# Demo_Board_3_-_Schematic.net
KiCad netlist of a schematic drawn in Altium Designer
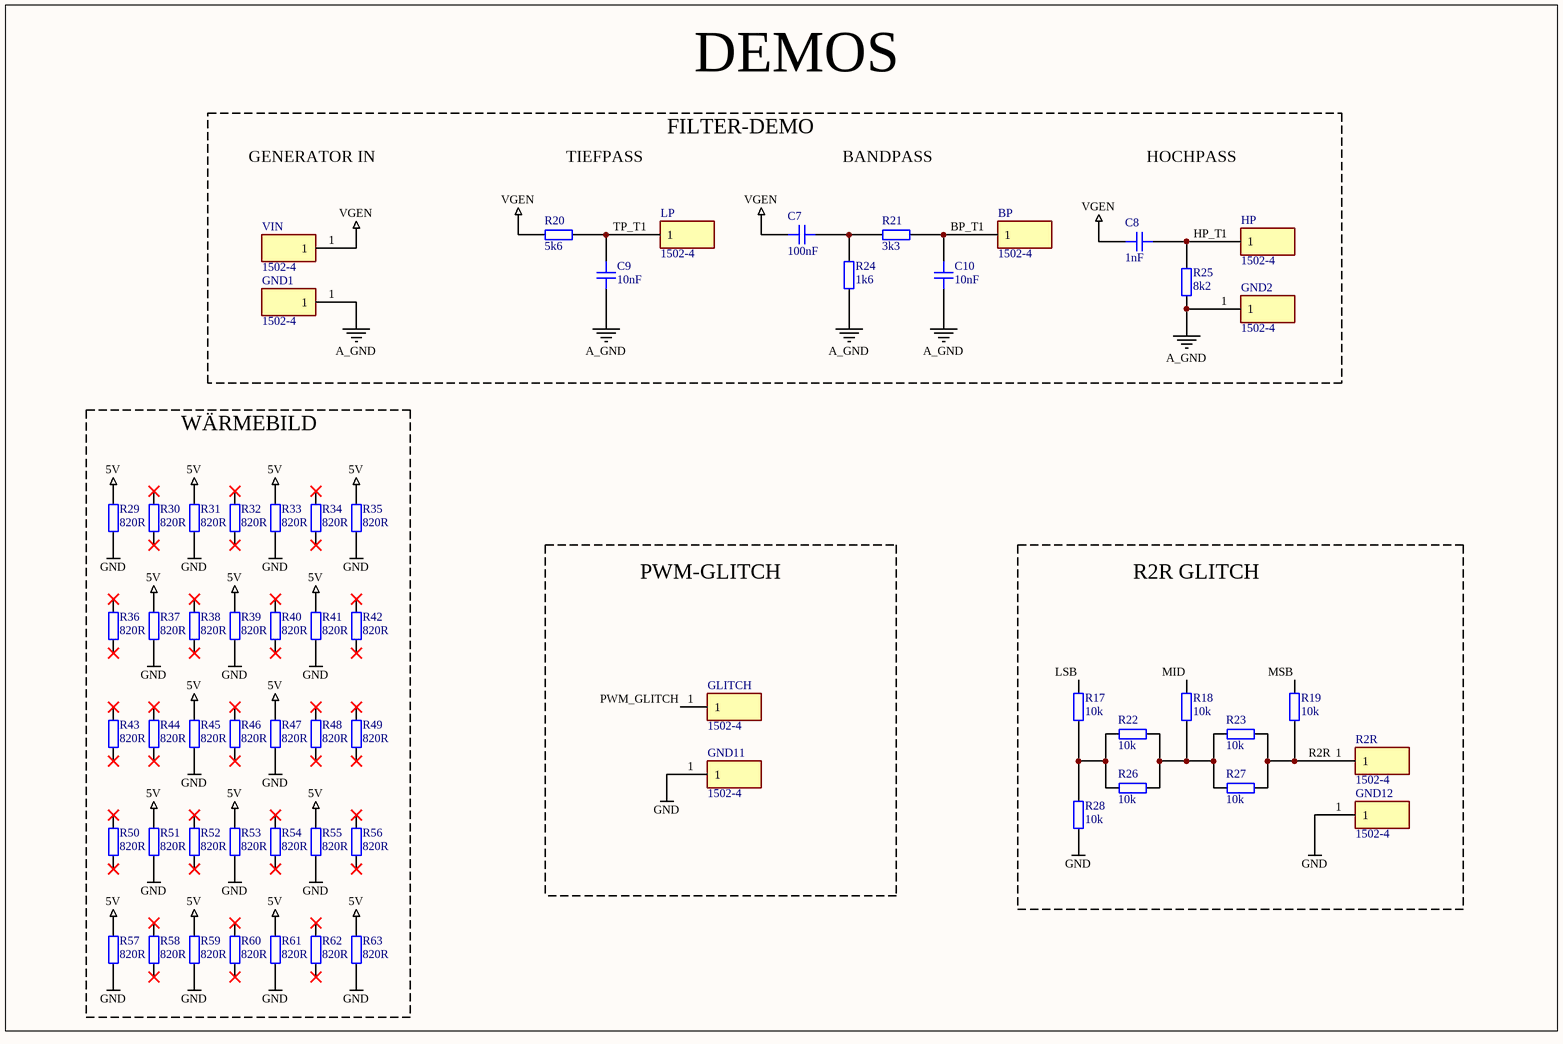
[diagram p0: Demo Board 3 - Schematic.SchDoc]

(export (version "E")
  (design (tool "Eeschema 10.0.6"))
  (components
    (comp (ref "BP")
      (value "1502-4")
      (footprint "KEYSTONE_1502-4")
      (libsource (lib "1502-4") (part "1502-4"))
    )
    (comp (ref "C7")
      (value "100nF")
      (footprint "CAP_0603")
      (description "Capacitor SMD 0603")
      (libsource (lib "Auer Library") (part "CAP_0603"))
    )
    (comp (ref "C8")
      (value "1nF")
      (footprint "CAP_0603")
      (description "Capacitor SMD 0603")
      (libsource (lib "Auer Library") (part "CAP_0603"))
    )
    (comp (ref "C9")
      (value "10nF")
      (footprint "CAP_0603")
      (description "Capacitor SMD 0603")
      (libsource (lib "Auer Library") (part "CAP_0603"))
    )
    (comp (ref "C10")
      (value "10nF")
      (footprint "CAP_0603")
      (description "Capacitor SMD 0603")
      (libsource (lib "Auer Library") (part "CAP_0603"))
    )
    (comp (ref "GLITCH")
      (value "1502-4")
      (footprint "KEYSTONE_1502-4")
      (libsource (lib "1502-4") (part "1502-4"))
    )
    (comp (ref "GND1") (value "1502-4") (footprint "KEYSTONE_1502-4") (libsource (lib "") (part "1502-4_1")))
    (comp (ref "GND2")
      (value "1502-4")
      (footprint "KEYSTONE_1502-4")
      (libsource (lib "1502-4") (part "1502-4"))
    )
    (comp (ref "GND11")
      (value "1502-4")
      (footprint "KEYSTONE_1502-4")
      (libsource (lib "1502-4") (part "1502-4"))
    )
    (comp (ref "GND12")
      (value "1502-4")
      (footprint "KEYSTONE_1502-4")
      (libsource (lib "1502-4") (part "1502-4"))
    )
    (comp (ref "HP")
      (value "1502-4")
      (footprint "KEYSTONE_1502-4")
      (libsource (lib "1502-4") (part "1502-4"))
    )
    (comp (ref "LP")
      (value "1502-4")
      (footprint "KEYSTONE_1502-4")
      (libsource (lib "1502-4") (part "1502-4"))
    )
    (comp (ref "R2R")
      (value "1502-4")
      (footprint "KEYSTONE_1502-4")
      (libsource (lib "1502-4") (part "1502-4"))
    )
    (comp (ref "R17")
      (value "10k")
      (footprint "RES_0603")
      (description "Resistor SMD 0603")
      (libsource (lib "Auer Library") (part "RES_0603"))
    )
    (comp (ref "R18")
      (value "10k")
      (footprint "RES_0603")
      (description "Resistor SMD 0603")
      (libsource (lib "Auer Library") (part "RES_0603"))
    )
    (comp (ref "R19")
      (value "10k")
      (footprint "RES_0603")
      (description "Resistor SMD 0603")
      (libsource (lib "Auer Library") (part "RES_0603"))
    )
    (comp (ref "R20")
      (value "5k6")
      (footprint "RES_0603")
      (description "Resistor SMD 0603")
      (libsource (lib "Auer Library") (part "RES_0603"))
    )
    (comp (ref "R21")
      (value "3k3")
      (footprint "RES_0603")
      (description "Resistor SMD 0603")
      (libsource (lib "Auer Library") (part "RES_0603"))
    )
    (comp (ref "R22")
      (value "10k")
      (footprint "RES_0603")
      (description "Resistor SMD 0603")
      (libsource (lib "Auer Library") (part "RES_0603"))
    )
    (comp (ref "R23")
      (value "10k")
      (footprint "RES_0603")
      (description "Resistor SMD 0603")
      (libsource (lib "Auer Library") (part "RES_0603"))
    )
    (comp (ref "R24")
      (value "1k6")
      (footprint "RES_0603")
      (description "Resistor SMD 0603")
      (libsource (lib "Auer Library") (part "RES_0603"))
    )
    (comp (ref "R25")
      (value "8k2")
      (footprint "RES_0603")
      (description "Resistor SMD 0603")
      (libsource (lib "Auer Library") (part "RES_0603"))
    )
    (comp (ref "R26")
      (value "10k")
      (footprint "RES_0603")
      (description "Resistor SMD 0603")
      (libsource (lib "Auer Library") (part "RES_0603"))
    )
    (comp (ref "R27")
      (value "10k")
      (footprint "RES_0603")
      (description "Resistor SMD 0603")
      (libsource (lib "Auer Library") (part "RES_0603"))
    )
    (comp (ref "R28")
      (value "10k")
      (footprint "RES_0603")
      (description "Resistor SMD 0603")
      (libsource (lib "Auer Library") (part "RES_0603"))
    )
    (comp (ref "R29")
      (value "820R")
      (footprint "RES_0603")
      (description "Resistor SMD 0603")
      (libsource (lib "Auer Library") (part "RES_0603"))
    )
    (comp (ref "R30")
      (value "820R")
      (footprint "RES_0603")
      (description "Resistor SMD 0603")
      (libsource (lib "Auer Library") (part "RES_0603"))
    )
    (comp (ref "R31")
      (value "820R")
      (footprint "RES_0603")
      (description "Resistor SMD 0603")
      (libsource (lib "Auer Library") (part "RES_0603"))
    )
    (comp (ref "R32")
      (value "820R")
      (footprint "RES_0603")
      (description "Resistor SMD 0603")
      (libsource (lib "Auer Library") (part "RES_0603"))
    )
    (comp (ref "R33")
      (value "820R")
      (footprint "RES_0603")
      (description "Resistor SMD 0603")
      (libsource (lib "Auer Library") (part "RES_0603"))
    )
    (comp (ref "R34")
      (value "820R")
      (footprint "RES_0603")
      (description "Resistor SMD 0603")
      (libsource (lib "Auer Library") (part "RES_0603"))
    )
    (comp (ref "R35")
      (value "820R")
      (footprint "RES_0603")
      (description "Resistor SMD 0603")
      (libsource (lib "Auer Library") (part "RES_0603"))
    )
    (comp (ref "R36")
      (value "820R")
      (footprint "RES_0603")
      (description "Resistor SMD 0603")
      (libsource (lib "Auer Library") (part "RES_0603"))
    )
    (comp (ref "R37")
      (value "820R")
      (footprint "RES_0603")
      (description "Resistor SMD 0603")
      (libsource (lib "Auer Library") (part "RES_0603"))
    )
    (comp (ref "R38")
      (value "820R")
      (footprint "RES_0603")
      (description "Resistor SMD 0603")
      (libsource (lib "Auer Library") (part "RES_0603"))
    )
    (comp (ref "R39")
      (value "820R")
      (footprint "RES_0603")
      (description "Resistor SMD 0603")
      (libsource (lib "Auer Library") (part "RES_0603"))
    )
    (comp (ref "R40")
      (value "820R")
      (footprint "RES_0603")
      (description "Resistor SMD 0603")
      (libsource (lib "Auer Library") (part "RES_0603"))
    )
    (comp (ref "R41")
      (value "820R")
      (footprint "RES_0603")
      (description "Resistor SMD 0603")
      (libsource (lib "Auer Library") (part "RES_0603"))
    )
    (comp (ref "R42")
      (value "820R")
      (footprint "RES_0603")
      (description "Resistor SMD 0603")
      (libsource (lib "Auer Library") (part "RES_0603"))
    )
    (comp (ref "R43")
      (value "820R")
      (footprint "RES_0603")
      (description "Resistor SMD 0603")
      (libsource (lib "Auer Library") (part "RES_0603"))
    )
    (comp (ref "R44")
      (value "820R")
      (footprint "RES_0603")
      (description "Resistor SMD 0603")
      (libsource (lib "Auer Library") (part "RES_0603"))
    )
    (comp (ref "R45")
      (value "820R")
      (footprint "RES_0603")
      (description "Resistor SMD 0603")
      (libsource (lib "Auer Library") (part "RES_0603"))
    )
    (comp (ref "R46")
      (value "820R")
      (footprint "RES_0603")
      (description "Resistor SMD 0603")
      (libsource (lib "Auer Library") (part "RES_0603"))
    )
    (comp (ref "R47")
      (value "820R")
      (footprint "RES_0603")
      (description "Resistor SMD 0603")
      (libsource (lib "Auer Library") (part "RES_0603"))
    )
    (comp (ref "R48")
      (value "820R")
      (footprint "RES_0603")
      (description "Resistor SMD 0603")
      (libsource (lib "Auer Library") (part "RES_0603"))
    )
    (comp (ref "R49")
      (value "820R")
      (footprint "RES_0603")
      (description "Resistor SMD 0603")
      (libsource (lib "Auer Library") (part "RES_0603"))
    )
    (comp (ref "R50")
      (value "820R")
      (footprint "RES_0603")
      (description "Resistor SMD 0603")
      (libsource (lib "Auer Library") (part "RES_0603"))
    )
    (comp (ref "R51")
      (value "820R")
      (footprint "RES_0603")
      (description "Resistor SMD 0603")
      (libsource (lib "Auer Library") (part "RES_0603"))
    )
    (comp (ref "R52")
      (value "820R")
      (footprint "RES_0603")
      (description "Resistor SMD 0603")
      (libsource (lib "Auer Library") (part "RES_0603"))
    )
    (comp (ref "R53")
      (value "820R")
      (footprint "RES_0603")
      (description "Resistor SMD 0603")
      (libsource (lib "Auer Library") (part "RES_0603"))
    )
    (comp (ref "R54")
      (value "820R")
      (footprint "RES_0603")
      (description "Resistor SMD 0603")
      (libsource (lib "Auer Library") (part "RES_0603"))
    )
    (comp (ref "R55")
      (value "820R")
      (footprint "RES_0603")
      (description "Resistor SMD 0603")
      (libsource (lib "Auer Library") (part "RES_0603"))
    )
    (comp (ref "R56")
      (value "820R")
      (footprint "RES_0603")
      (description "Resistor SMD 0603")
      (libsource (lib "Auer Library") (part "RES_0603"))
    )
    (comp (ref "R57")
      (value "820R")
      (footprint "RES_0603")
      (description "Resistor SMD 0603")
      (libsource (lib "Auer Library") (part "RES_0603"))
    )
    (comp (ref "R58")
      (value "820R")
      (footprint "RES_0603")
      (description "Resistor SMD 0603")
      (libsource (lib "Auer Library") (part "RES_0603"))
    )
    (comp (ref "R59")
      (value "820R")
      (footprint "RES_0603")
      (description "Resistor SMD 0603")
      (libsource (lib "Auer Library") (part "RES_0603"))
    )
    (comp (ref "R60")
      (value "820R")
      (footprint "RES_0603")
      (description "Resistor SMD 0603")
      (libsource (lib "Auer Library") (part "RES_0603"))
    )
    (comp (ref "R61")
      (value "820R")
      (footprint "RES_0603")
      (description "Resistor SMD 0603")
      (libsource (lib "Auer Library") (part "RES_0603"))
    )
    (comp (ref "R62")
      (value "820R")
      (footprint "RES_0603")
      (description "Resistor SMD 0603")
      (libsource (lib "Auer Library") (part "RES_0603"))
    )
    (comp (ref "R63")
      (value "820R")
      (footprint "RES_0603")
      (description "Resistor SMD 0603")
      (libsource (lib "Auer Library") (part "RES_0603"))
    )
    (comp (ref "VIN") (value "1502-4") (footprint "KEYSTONE_1502-4") (libsource (lib "") (part "1502-4_2")))
  )
  (nets
    (net (code "1") (name "/BP_T") (class "Default")
      (node (ref "BP") (pin "1") (pinfunction "1_1") (pintype "passive"))
      (node (ref "C10") (pin "1") (pinfunction "1_1") (pintype "passive"))
      (node (ref "R21") (pin "2") (pinfunction "2_2") (pintype "passive"))
    )
    (net (code "2") (name "/HP_T") (class "Default")
      (node (ref "C8") (pin "1") (pinfunction "1_1") (pintype "passive"))
      (node (ref "HP") (pin "1") (pinfunction "1_1") (pintype "passive"))
      (node (ref "R25") (pin "1") (pinfunction "1_1") (pintype "passive"))
    )
    (net (code "3") (name "/LSB") (class "Default")
      (node (ref "R17") (pin "2") (pinfunction "2_2") (pintype "passive"))
    )
    (net (code "4") (name "/MID") (class "Default")
      (node (ref "R18") (pin "2") (pinfunction "2_2") (pintype "passive"))
    )
    (net (code "5") (name "/MSB") (class "Default")
      (node (ref "R19") (pin "2") (pinfunction "2_2") (pintype "passive"))
    )
    (net (code "6") (name "/PWM_GLITCH") (class "Default")
      (node (ref "GLITCH") (pin "1") (pinfunction "1_1") (pintype "passive"))
    )
    (net (code "7") (name "/R2R") (class "Default")
      (node (ref "R19") (pin "1") (pinfunction "1_1") (pintype "passive"))
      (node (ref "R23") (pin "1") (pinfunction "1_1") (pintype "passive"))
      (node (ref "R27") (pin "1") (pinfunction "1_1") (pintype "passive"))
      (node (ref "R2R") (pin "1") (pinfunction "1_1") (pintype "passive"))
    )
    (net (code "8") (name "/TP_T") (class "Default")
      (node (ref "C9") (pin "2") (pinfunction "2_2") (pintype "passive"))
      (node (ref "LP") (pin "1") (pinfunction "1_1") (pintype "passive"))
      (node (ref "R20") (pin "1") (pinfunction "1_1") (pintype "passive"))
    )
    (net (code "9") (name "5V") (class "Default")
      (node (ref "R29") (pin "2") (pinfunction "2_2") (pintype "passive"))
      (node (ref "R31") (pin "2") (pinfunction "2_2") (pintype "passive"))
      (node (ref "R33") (pin "2") (pinfunction "2_2") (pintype "passive"))
      (node (ref "R35") (pin "2") (pinfunction "2_2") (pintype "passive"))
      (node (ref "R37") (pin "2") (pinfunction "2_2") (pintype "passive"))
      (node (ref "R39") (pin "2") (pinfunction "2_2") (pintype "passive"))
      (node (ref "R41") (pin "2") (pinfunction "2_2") (pintype "passive"))
      (node (ref "R45") (pin "2") (pinfunction "2_2") (pintype "passive"))
      (node (ref "R47") (pin "2") (pinfunction "2_2") (pintype "passive"))
      (node (ref "R51") (pin "2") (pinfunction "2_2") (pintype "passive"))
      (node (ref "R53") (pin "2") (pinfunction "2_2") (pintype "passive"))
      (node (ref "R55") (pin "2") (pinfunction "2_2") (pintype "passive"))
      (node (ref "R57") (pin "2") (pinfunction "2_2") (pintype "passive"))
      (node (ref "R59") (pin "2") (pinfunction "2_2") (pintype "passive"))
      (node (ref "R61") (pin "2") (pinfunction "2_2") (pintype "passive"))
      (node (ref "R63") (pin "2") (pinfunction "2_2") (pintype "passive"))
    )
    (net (code "10") (name "A_GND") (class "Default")
      (node (ref "C10") (pin "2") (pinfunction "2_2") (pintype "passive"))
      (node (ref "C9") (pin "1") (pinfunction "1_1") (pintype "passive"))
      (node (ref "GND1") (pin "1") (pinfunction "1_1") (pintype "passive"))
      (node (ref "GND2") (pin "1") (pinfunction "1_1") (pintype "passive"))
      (node (ref "R24") (pin "2") (pinfunction "2_2") (pintype "passive"))
      (node (ref "R25") (pin "2") (pinfunction "2_2") (pintype "passive"))
    )
    (net (code "11") (name "GND") (class "Default")
      (node (ref "GND11") (pin "1") (pinfunction "1_1") (pintype "passive"))
      (node (ref "GND12") (pin "1") (pinfunction "1_1") (pintype "passive"))
      (node (ref "R28") (pin "1") (pinfunction "1_1") (pintype "passive"))
      (node (ref "R29") (pin "1") (pinfunction "1_1") (pintype "passive"))
      (node (ref "R31") (pin "1") (pinfunction "1_1") (pintype "passive"))
      (node (ref "R33") (pin "1") (pinfunction "1_1") (pintype "passive"))
      (node (ref "R35") (pin "1") (pinfunction "1_1") (pintype "passive"))
      (node (ref "R37") (pin "1") (pinfunction "1_1") (pintype "passive"))
      (node (ref "R39") (pin "1") (pinfunction "1_1") (pintype "passive"))
      (node (ref "R41") (pin "1") (pinfunction "1_1") (pintype "passive"))
      (node (ref "R45") (pin "1") (pinfunction "1_1") (pintype "passive"))
      (node (ref "R47") (pin "1") (pinfunction "1_1") (pintype "passive"))
      (node (ref "R51") (pin "1") (pinfunction "1_1") (pintype "passive"))
      (node (ref "R53") (pin "1") (pinfunction "1_1") (pintype "passive"))
      (node (ref "R55") (pin "1") (pinfunction "1_1") (pintype "passive"))
      (node (ref "R57") (pin "1") (pinfunction "1_1") (pintype "passive"))
      (node (ref "R59") (pin "1") (pinfunction "1_1") (pintype "passive"))
      (node (ref "R61") (pin "1") (pinfunction "1_1") (pintype "passive"))
      (node (ref "R63") (pin "1") (pinfunction "1_1") (pintype "passive"))
    )
    (net (code "12") (name "Net-(C7-Pad1)") (class "Default")
      (node (ref "C7") (pin "1") (pinfunction "1_1") (pintype "passive"))
      (node (ref "R21") (pin "1") (pinfunction "1_1") (pintype "passive"))
      (node (ref "R24") (pin "1") (pinfunction "1_1") (pintype "passive"))
    )
    (net (code "13") (name "Net-(R17-Pad1)") (class "Default")
      (node (ref "R17") (pin "1") (pinfunction "1_1") (pintype "passive"))
      (node (ref "R22") (pin "2") (pinfunction "2_2") (pintype "passive"))
      (node (ref "R26") (pin "2") (pinfunction "2_2") (pintype "passive"))
      (node (ref "R28") (pin "2") (pinfunction "2_2") (pintype "passive"))
    )
    (net (code "14") (name "Net-(R18-Pad1)") (class "Default")
      (node (ref "R18") (pin "1") (pinfunction "1_1") (pintype "passive"))
      (node (ref "R22") (pin "1") (pinfunction "1_1") (pintype "passive"))
      (node (ref "R23") (pin "2") (pinfunction "2_2") (pintype "passive"))
      (node (ref "R26") (pin "1") (pinfunction "1_1") (pintype "passive"))
      (node (ref "R27") (pin "2") (pinfunction "2_2") (pintype "passive"))
    )
    (net (code "15") (name "VGEN") (class "Default")
      (node (ref "C7") (pin "2") (pinfunction "2_2") (pintype "passive"))
      (node (ref "C8") (pin "2") (pinfunction "2_2") (pintype "passive"))
      (node (ref "R20") (pin "2") (pinfunction "2_2") (pintype "passive"))
      (node (ref "VIN") (pin "1") (pinfunction "1_1") (pintype "passive"))
    )
    (net (code "16") (name "unconnected-(R30-Pad1)") (class "Default")
      (node (ref "R30") (pin "1") (pinfunction "1_1") (pintype "passive+no_connect"))
    )
    (net (code "17") (name "unconnected-(R30-Pad2)") (class "Default")
      (node (ref "R30") (pin "2") (pinfunction "2_2") (pintype "passive+no_connect"))
    )
    (net (code "18") (name "unconnected-(R32-Pad1)") (class "Default")
      (node (ref "R32") (pin "1") (pinfunction "1_1") (pintype "passive+no_connect"))
    )
    (net (code "19") (name "unconnected-(R32-Pad2)") (class "Default")
      (node (ref "R32") (pin "2") (pinfunction "2_2") (pintype "passive+no_connect"))
    )
    (net (code "20") (name "unconnected-(R34-Pad1)") (class "Default")
      (node (ref "R34") (pin "1") (pinfunction "1_1") (pintype "passive+no_connect"))
    )
    (net (code "21") (name "unconnected-(R34-Pad2)") (class "Default")
      (node (ref "R34") (pin "2") (pinfunction "2_2") (pintype "passive+no_connect"))
    )
    (net (code "22") (name "unconnected-(R36-Pad1)") (class "Default")
      (node (ref "R36") (pin "1") (pinfunction "1_1") (pintype "passive+no_connect"))
    )
    (net (code "23") (name "unconnected-(R36-Pad2)") (class "Default")
      (node (ref "R36") (pin "2") (pinfunction "2_2") (pintype "passive+no_connect"))
    )
    (net (code "24") (name "unconnected-(R38-Pad1)") (class "Default")
      (node (ref "R38") (pin "1") (pinfunction "1_1") (pintype "passive+no_connect"))
    )
    (net (code "25") (name "unconnected-(R38-Pad2)") (class "Default")
      (node (ref "R38") (pin "2") (pinfunction "2_2") (pintype "passive+no_connect"))
    )
    (net (code "26") (name "unconnected-(R40-Pad1)") (class "Default")
      (node (ref "R40") (pin "1") (pinfunction "1_1") (pintype "passive+no_connect"))
    )
    (net (code "27") (name "unconnected-(R40-Pad2)") (class "Default")
      (node (ref "R40") (pin "2") (pinfunction "2_2") (pintype "passive+no_connect"))
    )
    (net (code "28") (name "unconnected-(R42-Pad1)") (class "Default")
      (node (ref "R42") (pin "1") (pinfunction "1_1") (pintype "passive+no_connect"))
    )
    (net (code "29") (name "unconnected-(R42-Pad2)") (class "Default")
      (node (ref "R42") (pin "2") (pinfunction "2_2") (pintype "passive+no_connect"))
    )
    (net (code "30") (name "unconnected-(R43-Pad1)") (class "Default")
      (node (ref "R43") (pin "1") (pinfunction "1_1") (pintype "passive+no_connect"))
    )
    (net (code "31") (name "unconnected-(R43-Pad2)") (class "Default")
      (node (ref "R43") (pin "2") (pinfunction "2_2") (pintype "passive+no_connect"))
    )
    (net (code "32") (name "unconnected-(R44-Pad1)") (class "Default")
      (node (ref "R44") (pin "1") (pinfunction "1_1") (pintype "passive+no_connect"))
    )
    (net (code "33") (name "unconnected-(R44-Pad2)") (class "Default")
      (node (ref "R44") (pin "2") (pinfunction "2_2") (pintype "passive+no_connect"))
    )
    (net (code "34") (name "unconnected-(R46-Pad1)") (class "Default")
      (node (ref "R46") (pin "1") (pinfunction "1_1") (pintype "passive+no_connect"))
    )
    (net (code "35") (name "unconnected-(R46-Pad2)") (class "Default")
      (node (ref "R46") (pin "2") (pinfunction "2_2") (pintype "passive+no_connect"))
    )
    (net (code "36") (name "unconnected-(R48-Pad1)") (class "Default")
      (node (ref "R48") (pin "1") (pinfunction "1_1") (pintype "passive+no_connect"))
    )
    (net (code "37") (name "unconnected-(R48-Pad2)") (class "Default")
      (node (ref "R48") (pin "2") (pinfunction "2_2") (pintype "passive+no_connect"))
    )
    (net (code "38") (name "unconnected-(R49-Pad1)") (class "Default")
      (node (ref "R49") (pin "1") (pinfunction "1_1") (pintype "passive+no_connect"))
    )
    (net (code "39") (name "unconnected-(R49-Pad2)") (class "Default")
      (node (ref "R49") (pin "2") (pinfunction "2_2") (pintype "passive+no_connect"))
    )
    (net (code "40") (name "unconnected-(R50-Pad1)") (class "Default")
      (node (ref "R50") (pin "1") (pinfunction "1_1") (pintype "passive+no_connect"))
    )
    (net (code "41") (name "unconnected-(R50-Pad2)") (class "Default")
      (node (ref "R50") (pin "2") (pinfunction "2_2") (pintype "passive+no_connect"))
    )
    (net (code "42") (name "unconnected-(R52-Pad1)") (class "Default")
      (node (ref "R52") (pin "1") (pinfunction "1_1") (pintype "passive+no_connect"))
    )
    (net (code "43") (name "unconnected-(R52-Pad2)") (class "Default")
      (node (ref "R52") (pin "2") (pinfunction "2_2") (pintype "passive+no_connect"))
    )
    (net (code "44") (name "unconnected-(R54-Pad1)") (class "Default")
      (node (ref "R54") (pin "1") (pinfunction "1_1") (pintype "passive+no_connect"))
    )
    (net (code "45") (name "unconnected-(R54-Pad2)") (class "Default")
      (node (ref "R54") (pin "2") (pinfunction "2_2") (pintype "passive+no_connect"))
    )
    (net (code "46") (name "unconnected-(R56-Pad1)") (class "Default")
      (node (ref "R56") (pin "1") (pinfunction "1_1") (pintype "passive+no_connect"))
    )
    (net (code "47") (name "unconnected-(R56-Pad2)") (class "Default")
      (node (ref "R56") (pin "2") (pinfunction "2_2") (pintype "passive+no_connect"))
    )
    (net (code "48") (name "unconnected-(R58-Pad1)") (class "Default")
      (node (ref "R58") (pin "1") (pinfunction "1_1") (pintype "passive+no_connect"))
    )
    (net (code "49") (name "unconnected-(R58-Pad2)") (class "Default")
      (node (ref "R58") (pin "2") (pinfunction "2_2") (pintype "passive+no_connect"))
    )
    (net (code "50") (name "unconnected-(R60-Pad1)") (class "Default")
      (node (ref "R60") (pin "1") (pinfunction "1_1") (pintype "passive+no_connect"))
    )
    (net (code "51") (name "unconnected-(R60-Pad2)") (class "Default")
      (node (ref "R60") (pin "2") (pinfunction "2_2") (pintype "passive+no_connect"))
    )
    (net (code "52") (name "unconnected-(R62-Pad1)") (class "Default")
      (node (ref "R62") (pin "1") (pinfunction "1_1") (pintype "passive+no_connect"))
    )
    (net (code "53") (name "unconnected-(R62-Pad2)") (class "Default")
      (node (ref "R62") (pin "2") (pinfunction "2_2") (pintype "passive+no_connect"))
    )
  )
)
